# DB9_2_JST_GH.net
KiCad netlist of a schematic drawn in EAGLE
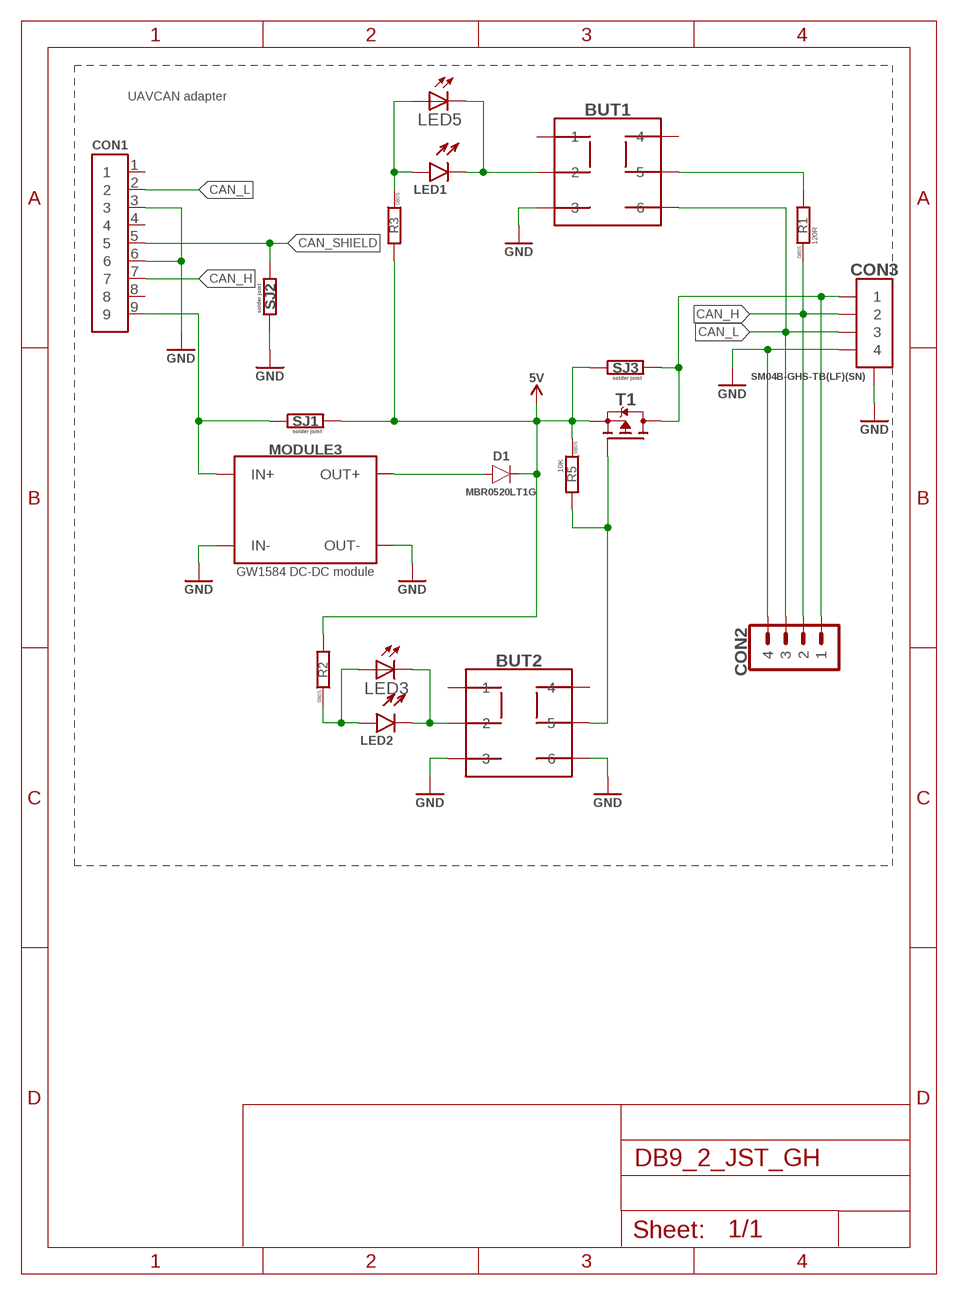
[diagram p0: schematic, sheet 1]

(export (version "E")
  (design (tool "Eeschema 10.0.6"))
  (components
    (comp (ref "BUT1")
      (value "BUTTON")
      (footprint "eagle-import:PBM-0112")
      (libsource (lib "eagle-import") (part "BUTTON"))
    )
    (comp (ref "BUT2")
      (value "BUTTON")
      (footprint "eagle-import:PBM-0112")
      (libsource (lib "eagle-import") (part "BUTTON"))
    )
    (comp (ref "CON1")
      (value "DB9")
      (footprint "eagle-import:D_SUB9")
      (libsource (lib "eagle-import") (part "DB9"))
    )
    (comp (ref "CON2")
      (value "PINHEAD_1X04-2.54")
      (footprint "eagle-import:1X04-PTH-2.54")
      (libsource (lib "eagle-import") (part "PINHEAD_1X04-2.54"))
    )
    (comp (ref "CON3")
      (value "CON-4P-JST_GH")
      (footprint "eagle-import:JST_GH-4P")
      (fields (field (name "MANF") "JST Sales America Inc"))
      (libsource (lib "eagle-import") (part "CON-4P-JST_GH"))
    )
    (comp (ref "D1")
      (value "MBR0520L-SOD123")
      (footprint "eagle-import:SOD123")
      (fields (field (name "MANF") "ON Semiconductor"))
      (libsource (lib "eagle-import") (part "MBR0520L-SOD123"))
    )
    (comp (ref "LED1")
      (value "LED-0805")
      (footprint "eagle-import:LED0805")
      (fields (field (name "COLOR") "RED"))
      (libsource (lib "eagle-import") (part "rc_LED-0805"))
    )
    (comp (ref "LED2")
      (value "LED-0805")
      (footprint "eagle-import:LED0805")
      (fields (field (name "COLOR") "YELLOW"))
      (libsource (lib "eagle-import") (part "rc_LED-0805"))
    )
    (comp (ref "LED3")
      (value "LED-3MM")
      (footprint "eagle-import:LED-3MM")
      (fields (field (name "ASSEMBLY") "SPECIAL"))
      (libsource (lib "eagle-import") (part "LED-3MM"))
    )
    (comp (ref "LED5")
      (value "LED-3MM")
      (footprint "eagle-import:LED-3MM")
      (fields (field (name "ASSEMBLY") "SPECIAL"))
      (libsource (lib "eagle-import") (part "LED-3MM"))
    )
    (comp (ref "MODULE3")
      (value "GW1584")
      (footprint "eagle-import:GW1584")
      (libsource (lib "eagle-import") (part "GW1584"))
    )
    (comp (ref "R1")
      (value "120R")
      (footprint "eagle-import:R0805")
      (libsource (lib "eagle-import") (part "R-0805"))
    )
    (comp (ref "R2")
      (value "R-0805")
      (footprint "eagle-import:R0805")
      (libsource (lib "eagle-import") (part "R-0805"))
    )
    (comp (ref "R3")
      (value "R-0805")
      (footprint "eagle-import:R0805")
      (libsource (lib "eagle-import") (part "R-0805"))
    )
    (comp (ref "R5")
      (value "10K")
      (footprint "eagle-import:R0805")
      (libsource (lib "eagle-import") (part "R-0805"))
    )
    (comp (ref "SJ1")
      (value "SOLDER_JOINT_2P")
      (footprint "eagle-import:SJ_2P")
      (libsource (lib "eagle-import") (part "SOLDER_JOINT_2P"))
    )
    (comp (ref "SJ2")
      (value "SOLDER_JOINT_2P")
      (footprint "eagle-import:SJ_2P")
      (libsource (lib "eagle-import") (part "SOLDER_JOINT_2P"))
    )
    (comp (ref "SJ3")
      (value "SOLDER_JOINT_2P")
      (footprint "eagle-import:SJ_2P")
      (libsource (lib "eagle-import") (part "SOLDER_JOINT_2P"))
    )
    (comp (ref "T1")
      (value "FDN302P-SOT23")
      (footprint "eagle-import:SOT23B-3")
      (fields (field (name "MANF") "Fairchild Semiconductor"))
      (libsource (lib "eagle-import") (part "FDN302P-SOT23"))
    )
  )
  (nets
    (net (code "1") (name "5V") (class "Default")
      (node (ref "D1") (pin "C") (pinfunction "C_C") (pintype "passive"))
      (node (ref "R2") (pin "2") (pinfunction "2_2") (pintype "passive"))
      (node (ref "R3") (pin "2") (pinfunction "2_2") (pintype "passive"))
      (node (ref "R5") (pin "1") (pinfunction "1_1") (pintype "passive"))
      (node (ref "SJ1") (pin "2") (pinfunction "2_2") (pintype "passive"))
      (node (ref "SJ3") (pin "1") (pinfunction "1_1") (pintype "passive"))
      (node (ref "T1") (pin "S") (pinfunction "S_S") (pintype "passive"))
    )
    (net (code "2") (name "CAN_H") (class "Default")
      (node (ref "CON1") (pin "7") (pinfunction "7_7") (pintype "bidirectional"))
      (node (ref "CON2") (pin "2") (pinfunction "2_2") (pintype "passive"))
      (node (ref "CON3") (pin "2") (pinfunction "2_2") (pintype "bidirectional"))
      (node (ref "R1") (pin "1") (pinfunction "1_1") (pintype "passive"))
    )
    (net (code "3") (name "CAN_L") (class "Default")
      (node (ref "BUT1") (pin "6") (pinfunction "6_6") (pintype "bidirectional"))
      (node (ref "CON1") (pin "2") (pinfunction "2_2") (pintype "bidirectional"))
      (node (ref "CON2") (pin "3") (pinfunction "3_3") (pintype "passive"))
      (node (ref "CON3") (pin "3") (pinfunction "3_3") (pintype "bidirectional"))
    )
    (net (code "4") (name "CAN_SHIELD") (class "Default")
      (node (ref "CON1") (pin "5") (pinfunction "5_5") (pintype "bidirectional"))
      (node (ref "SJ2") (pin "1") (pinfunction "1_1") (pintype "passive"))
    )
    (net (code "5") (name "GND") (class "Default")
      (node (ref "BUT1") (pin "3") (pinfunction "3_3") (pintype "bidirectional"))
      (node (ref "BUT2") (pin "3") (pinfunction "3_3") (pintype "bidirectional"))
      (node (ref "BUT2") (pin "6") (pinfunction "6_6") (pintype "bidirectional"))
      (node (ref "CON1") (pin "3") (pinfunction "3_3") (pintype "bidirectional"))
      (node (ref "CON1") (pin "6") (pinfunction "6_6") (pintype "bidirectional"))
      (node (ref "CON2") (pin "4") (pinfunction "4_4") (pintype "passive"))
      (node (ref "CON3") (pin "4") (pinfunction "4_4") (pintype "bidirectional"))
      (node (ref "CON3") (pin "M$0") (pinfunction "GND_M$0") (pintype "bidirectional"))
      (node (ref "CON3") (pin "M$1") (pinfunction "GND_M$1") (pintype "bidirectional"))
      (node (ref "MODULE3") (pin "IN-@1") (pinfunction "IN-_IN-@1") (pintype "bidirectional"))
      (node (ref "MODULE3") (pin "IN-@2") (pinfunction "IN-_IN-@2") (pintype "bidirectional"))
      (node (ref "MODULE3") (pin "OUT-@1") (pinfunction "OUT-_OUT-@1") (pintype "bidirectional"))
      (node (ref "MODULE3") (pin "OUT-@2") (pinfunction "OUT-_OUT-@2") (pintype "bidirectional"))
      (node (ref "SJ2") (pin "2") (pinfunction "2_2") (pintype "passive"))
    )
    (net (code "6") (name "Net-(BUT1-Pad5)") (class "Default")
      (node (ref "BUT1") (pin "5") (pinfunction "5_5") (pintype "bidirectional"))
      (node (ref "R1") (pin "2") (pinfunction "2_2") (pintype "passive"))
    )
    (net (code "7") (name "Net-(BUT2-Pad5)") (class "Default")
      (node (ref "BUT2") (pin "5") (pinfunction "5_5") (pintype "bidirectional"))
      (node (ref "R5") (pin "2") (pinfunction "2_2") (pintype "passive"))
      (node (ref "T1") (pin "G") (pinfunction "G_G") (pintype "passive"))
    )
    (net (code "8") (name "Net-(CON1-Pad9)") (class "Default")
      (node (ref "CON1") (pin "9") (pinfunction "9_9") (pintype "bidirectional"))
      (node (ref "MODULE3") (pin "IN+@1") (pinfunction "IN+_IN+@1") (pintype "bidirectional"))
      (node (ref "MODULE3") (pin "IN+@2") (pinfunction "IN+_IN+@2") (pintype "bidirectional"))
      (node (ref "SJ1") (pin "1") (pinfunction "1_1") (pintype "passive"))
    )
    (net (code "9") (name "Net-(CON2-Pad1)") (class "Default")
      (node (ref "CON2") (pin "1") (pinfunction "1_1") (pintype "passive"))
      (node (ref "CON3") (pin "1") (pinfunction "1_1") (pintype "bidirectional"))
      (node (ref "SJ3") (pin "2") (pinfunction "2_2") (pintype "passive"))
      (node (ref "T1") (pin "D") (pinfunction "D_D") (pintype "passive"))
    )
    (net (code "10") (name "Net-(D1-PadA)") (class "Default")
      (node (ref "D1") (pin "A") (pinfunction "A_A") (pintype "passive"))
      (node (ref "MODULE3") (pin "OUT+@1") (pinfunction "OUT+_OUT+@1") (pintype "bidirectional"))
      (node (ref "MODULE3") (pin "OUT+@2") (pinfunction "OUT+_OUT+@2") (pintype "bidirectional"))
    )
    (net (code "11") (name "Net-(LED1-PadA)") (class "Default")
      (node (ref "LED1") (pin "A") (pinfunction "A_A") (pintype "bidirectional"))
      (node (ref "LED5") (pin "A") (pinfunction "A_A") (pintype "passive"))
      (node (ref "R3") (pin "1") (pinfunction "1_1") (pintype "passive"))
    )
    (net (code "12") (name "Net-(LED2-PadA)") (class "Default")
      (node (ref "LED2") (pin "A") (pinfunction "A_A") (pintype "bidirectional"))
      (node (ref "LED3") (pin "A") (pinfunction "A_A") (pintype "passive"))
      (node (ref "R2") (pin "1") (pinfunction "1_1") (pintype "passive"))
    )
    (net (code "13") (name "Net-(LED3-C)") (class "Default")
      (node (ref "BUT2") (pin "2") (pinfunction "2_2") (pintype "bidirectional"))
      (node (ref "LED2") (pin "C") (pinfunction "C_C") (pintype "bidirectional"))
      (node (ref "LED3") (pin "K") (pinfunction "C_K") (pintype "passive"))
    )
    (net (code "14") (name "Net-(LED5-C)") (class "Default")
      (node (ref "BUT1") (pin "2") (pinfunction "2_2") (pintype "bidirectional"))
      (node (ref "LED1") (pin "C") (pinfunction "C_C") (pintype "bidirectional"))
      (node (ref "LED5") (pin "K") (pinfunction "C_K") (pintype "passive"))
    )
    (net (code "15") (name "unconnected-(BUT1-Pad1)") (class "Default")
      (node (ref "BUT1") (pin "1") (pinfunction "1_1") (pintype "bidirectional"))
    )
    (net (code "16") (name "unconnected-(BUT1-Pad4)") (class "Default")
      (node (ref "BUT1") (pin "4") (pinfunction "4_4") (pintype "bidirectional"))
    )
    (net (code "17") (name "unconnected-(BUT2-Pad1)") (class "Default")
      (node (ref "BUT2") (pin "1") (pinfunction "1_1") (pintype "bidirectional"))
    )
    (net (code "18") (name "unconnected-(BUT2-Pad4)") (class "Default")
      (node (ref "BUT2") (pin "4") (pinfunction "4_4") (pintype "bidirectional"))
    )
    (net (code "19") (name "unconnected-(CON1-Pad1)") (class "Default")
      (node (ref "CON1") (pin "1") (pinfunction "1_1") (pintype "bidirectional"))
    )
    (net (code "20") (name "unconnected-(CON1-Pad4)") (class "Default")
      (node (ref "CON1") (pin "4") (pinfunction "4_4") (pintype "bidirectional"))
    )
    (net (code "21") (name "unconnected-(CON1-Pad8)") (class "Default")
      (node (ref "CON1") (pin "8") (pinfunction "8_8") (pintype "bidirectional"))
    )
  )
)
